# L293d-BreakOut.net
KiCad netlist of a schematic drawn in EAGLE
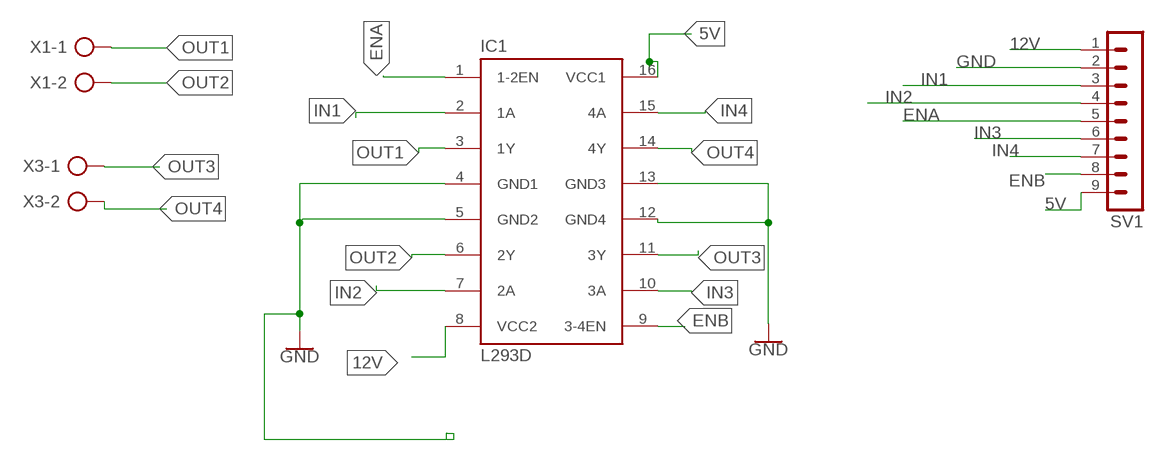
[diagram p0: schematic, sheet 1]

(export (version "E")
  (design (tool "Eeschema 10.0.6"))
  (components
    (comp (ref "IC1")
      (value "L293D")
      (footprint "eagle-import:DIL16")
      (libsource (lib "eagle-import") (part "L293D"))
    )
    (comp (ref "SV1")
      (value "MA09-1W")
      (footprint "eagle-import:MA09-1W")
      (libsource (lib "eagle-import") (part "MA09-1W"))
    )
    (comp (ref "X1")
      (value "AK500/2-H")
      (footprint "eagle-import:AK500_2-H")
      (libsource (lib "eagle-import") (part "AK500/2-H"))
    )
    (comp (ref "X3")
      (value "AK500/2-H")
      (footprint "eagle-import:AK500_2-H")
      (libsource (lib "eagle-import") (part "AK500/2-H"))
    )
  )
  (nets
    (net (code "1") (name "5V") (class "Default")
      (node (ref "IC1") (pin "16") (pinfunction "VCC1_16") (pintype "power_in"))
      (node (ref "SV1") (pin "9") (pinfunction "9_9") (pintype "passive"))
    )
    (net (code "2") (name "12V") (class "Default")
      (node (ref "IC1") (pin "8") (pinfunction "VCC2_8") (pintype "power_in"))
      (node (ref "SV1") (pin "1") (pinfunction "1_1") (pintype "passive"))
    )
    (net (code "3") (name "ENA") (class "Default")
      (node (ref "IC1") (pin "1") (pinfunction "1-2EN_1") (pintype "input"))
      (node (ref "SV1") (pin "5") (pinfunction "5_5") (pintype "passive"))
    )
    (net (code "4") (name "ENB") (class "Default")
      (node (ref "IC1") (pin "9") (pinfunction "3-4EN_9") (pintype "input"))
      (node (ref "SV1") (pin "8") (pinfunction "8_8") (pintype "passive"))
    )
    (net (code "5") (name "GND") (class "Default")
      (node (ref "IC1") (pin "12") (pinfunction "GND4_12") (pintype "power_in"))
      (node (ref "IC1") (pin "13") (pinfunction "GND3_13") (pintype "power_in"))
      (node (ref "IC1") (pin "4") (pinfunction "GND1_4") (pintype "power_in"))
      (node (ref "IC1") (pin "5") (pinfunction "GND2_5") (pintype "power_in"))
      (node (ref "SV1") (pin "2") (pinfunction "2_2") (pintype "passive"))
    )
    (net (code "6") (name "IN1") (class "Default")
      (node (ref "IC1") (pin "2") (pinfunction "1A_2") (pintype "input"))
      (node (ref "SV1") (pin "3") (pinfunction "3_3") (pintype "passive"))
    )
    (net (code "7") (name "IN2") (class "Default")
      (node (ref "IC1") (pin "7") (pinfunction "2A_7") (pintype "input"))
      (node (ref "SV1") (pin "4") (pinfunction "4_4") (pintype "passive"))
    )
    (net (code "8") (name "IN3") (class "Default")
      (node (ref "IC1") (pin "10") (pinfunction "3A_10") (pintype "input"))
      (node (ref "SV1") (pin "6") (pinfunction "6_6") (pintype "passive"))
    )
    (net (code "9") (name "IN4") (class "Default")
      (node (ref "IC1") (pin "15") (pinfunction "4A_15") (pintype "input"))
      (node (ref "SV1") (pin "7") (pinfunction "7_7") (pintype "passive"))
    )
    (net (code "10") (name "OUT1") (class "Default")
      (node (ref "IC1") (pin "3") (pinfunction "1Y_3") (pintype "output"))
      (node (ref "X1") (pin "1") (pinfunction "KL_1") (pintype "passive"))
    )
    (net (code "11") (name "OUT2") (class "Default")
      (node (ref "IC1") (pin "6") (pinfunction "2Y_6") (pintype "output"))
      (node (ref "X1") (pin "2") (pinfunction "KL_2") (pintype "passive"))
    )
    (net (code "12") (name "OUT3") (class "Default")
      (node (ref "IC1") (pin "11") (pinfunction "3Y_11") (pintype "output"))
      (node (ref "X3") (pin "1") (pinfunction "KL_1") (pintype "passive"))
    )
    (net (code "13") (name "OUT4") (class "Default")
      (node (ref "IC1") (pin "14") (pinfunction "4Y_14") (pintype "output"))
      (node (ref "X3") (pin "2") (pinfunction "KL_2") (pintype "passive"))
    )
  )
)
